# JDA_Compact_Switch_V2.net
KiCad netlist of a schematic drawn in EAGLE
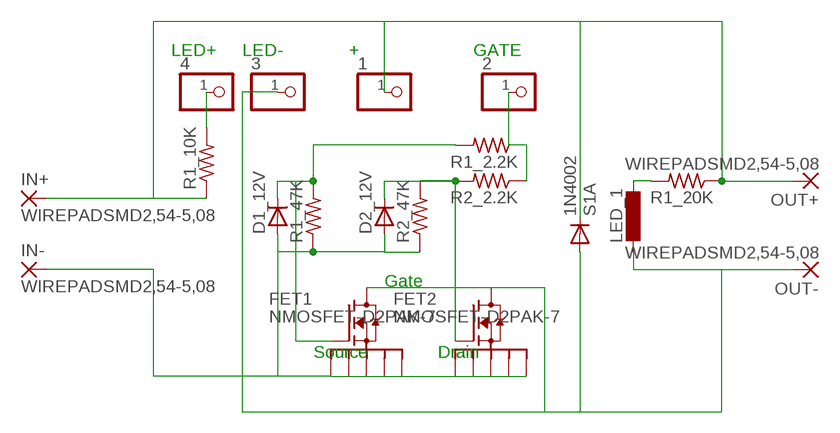
[diagram p0: schematic, sheet 1]

(export (version "E")
  (design (tool "Eeschema 10.0.6"))
  (components
    (comp (ref "1")
      (value "PINHD-1X1")
      (footprint "eagle-import:1X01")
      (libsource (lib "eagle-import") (part "PINHD-1X1"))
    )
    (comp (ref "1N4002")
      (value "S1A")
      (footprint "eagle-import:DO214AC")
      (fields (field (name "MF") "Fairchild"))
      (libsource (lib "eagle-import") (part "S1A"))
    )
    (comp (ref "2")
      (value "PINHD-1X1")
      (footprint "eagle-import:1X01")
      (libsource (lib "eagle-import") (part "PINHD-1X1"))
    )
    (comp (ref "3")
      (value "PINHD-1X1")
      (footprint "eagle-import:1X01")
      (libsource (lib "eagle-import") (part "PINHD-1X1"))
    )
    (comp (ref "4")
      (value "PINHD-1X1")
      (footprint "eagle-import:1X01")
      (libsource (lib "eagle-import") (part "PINHD-1X1"))
    )
    (comp (ref "D1_12V")
      (value "D-SOD-80")
      (footprint "eagle-import:SOD80")
      (libsource (lib "eagle-import") (part "D-SOD-80"))
    )
    (comp (ref "D2_12V")
      (value "D-SOD-80")
      (footprint "eagle-import:SOD80")
      (libsource (lib "eagle-import") (part "D-SOD-80"))
    )
    (comp (ref "FET1")
      (value "NMOSFET-D2PAK-7")
      (footprint "eagle-import:D2PAK-7")
      (libsource (lib "eagle-import") (part "NMOSFET-D2PAK-7"))
    )
    (comp (ref "FET2")
      (value "NMOSFET-D2PAK-7")
      (footprint "eagle-import:D2PAK-7")
      (libsource (lib "eagle-import") (part "NMOSFET-D2PAK-7"))
    )
    (comp (ref "IN+")
      (value "WIREPADSMD2,54-5,08")
      (footprint "eagle-import:SMD2,54-5,08")
      (libsource (lib "eagle-import") (part "WIREPADSMD2,54-5,08"))
    )
    (comp (ref "IN-")
      (value "WIREPADSMD2,54-5,08")
      (footprint "eagle-import:SMD2,54-5,08")
      (libsource (lib "eagle-import") (part "WIREPADSMD2,54-5,08"))
    )
    (comp (ref "LED_1")
      (value "L-EUL0805")
      (footprint "eagle-import:L0805")
      (libsource (lib "eagle-import") (part "L-EUL0805"))
    )
    (comp (ref "OUT+")
      (value "WIREPADSMD2,54-5,08")
      (footprint "eagle-import:SMD2,54-5,08")
      (libsource (lib "eagle-import") (part "WIREPADSMD2,54-5,08"))
    )
    (comp (ref "OUT-")
      (value "WIREPADSMD2,54-5,08")
      (footprint "eagle-import:SMD2,54-5,08")
      (libsource (lib "eagle-import") (part "WIREPADSMD2,54-5,08"))
    )
    (comp (ref "R1_2.2K")
      (value "R-US_M1206")
      (footprint "eagle-import:M1206")
      (libsource (lib "eagle-import") (part "resistor_R-US_M1206"))
    )
    (comp (ref "R1_10K")
      (value "R-US_M1206")
      (footprint "eagle-import:M1206")
      (libsource (lib "eagle-import") (part "resistor_R-US_M1206"))
    )
    (comp (ref "R1_20K")
      (value "R-US_R1206")
      (footprint "eagle-import:R1206")
      (libsource (lib "eagle-import") (part "R-US_R1206"))
    )
    (comp (ref "R1_47K")
      (value "R-US_M1206")
      (footprint "eagle-import:M1206")
      (libsource (lib "eagle-import") (part "resistor_R-US_M1206"))
    )
    (comp (ref "R2_2.2K")
      (value "R-US_M1206")
      (footprint "eagle-import:M1206")
      (libsource (lib "eagle-import") (part "resistor_R-US_M1206"))
    )
    (comp (ref "R2_47K")
      (value "R-US_M1206")
      (footprint "eagle-import:M1206")
      (libsource (lib "eagle-import") (part "resistor_R-US_M1206"))
    )
  )
  (nets
    (net (code "1") (name "Net-(2-Pad1)") (class "Default")
      (node (ref "2") (pin "1") (pinfunction "1_1") (pintype "passive"))
      (node (ref "R1_2.2K") (pin "1") (pinfunction "1_1") (pintype "passive"))
      (node (ref "R2_2.2K") (pin "1") (pinfunction "1_1") (pintype "passive"))
    )
    (net (code "2") (name "Net-(4-Pad1)") (class "Default")
      (node (ref "4") (pin "1") (pinfunction "1_1") (pintype "passive"))
      (node (ref "R1_10K") (pin "2") (pinfunction "2_2") (pintype "passive"))
    )
    (net (code "3") (name "Net-(D1_12V-PadC)") (class "Default")
      (node (ref "D1_12V") (pin "C") (pinfunction "C_C") (pintype "passive"))
      (node (ref "FET1") (pin "G") (pinfunction "G_G") (pintype "passive"))
      (node (ref "R1_2.2K") (pin "2") (pinfunction "2_2") (pintype "passive"))
      (node (ref "R1_47K") (pin "2") (pinfunction "2_2") (pintype "passive"))
    )
    (net (code "4") (name "Net-(D2_12V-PadC)") (class "Default")
      (node (ref "D2_12V") (pin "C") (pinfunction "C_C") (pintype "passive"))
      (node (ref "FET2") (pin "G") (pinfunction "G_G") (pintype "passive"))
      (node (ref "R2_2.2K") (pin "2") (pinfunction "2_2") (pintype "passive"))
      (node (ref "R2_47K") (pin "2") (pinfunction "2_2") (pintype "passive"))
    )
    (net (code "5") (name "Net-(IN+-P)") (class "Default")
      (node (ref "1") (pin "1") (pinfunction "1_1") (pintype "passive"))
      (node (ref "1N4002") (pin "C") (pinfunction "C_C") (pintype "passive"))
      (node (ref "IN+") (pin "1") (pinfunction "P_1") (pintype "passive"))
      (node (ref "OUT+") (pin "1") (pinfunction "P_1") (pintype "passive"))
      (node (ref "R1_10K") (pin "1") (pinfunction "1_1") (pintype "passive"))
      (node (ref "R1_20K") (pin "1") (pinfunction "1_1") (pintype "passive"))
    )
    (net (code "6") (name "Net-(IN--P)") (class "Default")
      (node (ref "D1_12V") (pin "A") (pinfunction "A_A") (pintype "passive"))
      (node (ref "D2_12V") (pin "A") (pinfunction "A_A") (pintype "passive"))
      (node (ref "FET1") (pin "S1") (pinfunction "S1_S1") (pintype "passive"))
      (node (ref "FET1") (pin "S2") (pinfunction "S2_S2") (pintype "passive"))
      (node (ref "FET1") (pin "S3") (pinfunction "S3_S3") (pintype "passive"))
      (node (ref "FET1") (pin "S4") (pinfunction "S4_S4") (pintype "passive"))
      (node (ref "FET1") (pin "S5") (pinfunction "S5_S5") (pintype "passive"))
      (node (ref "FET2") (pin "S1") (pinfunction "S1_S1") (pintype "passive"))
      (node (ref "FET2") (pin "S2") (pinfunction "S2_S2") (pintype "passive"))
      (node (ref "FET2") (pin "S3") (pinfunction "S3_S3") (pintype "passive"))
      (node (ref "FET2") (pin "S4") (pinfunction "S4_S4") (pintype "passive"))
      (node (ref "FET2") (pin "S5") (pinfunction "S5_S5") (pintype "passive"))
      (node (ref "IN-") (pin "1") (pinfunction "P_1") (pintype "passive"))
      (node (ref "R1_47K") (pin "1") (pinfunction "1_1") (pintype "passive"))
      (node (ref "R2_47K") (pin "1") (pinfunction "1_1") (pintype "passive"))
    )
    (net (code "7") (name "Net-(LED_1-Pad1)") (class "Default")
      (node (ref "LED_1") (pin "1") (pinfunction "1_1") (pintype "passive"))
      (node (ref "R1_20K") (pin "2") (pinfunction "2_2") (pintype "passive"))
    )
    (net (code "8") (name "Net-(OUT--P)") (class "Default")
      (node (ref "1N4002") (pin "A") (pinfunction "A_A") (pintype "passive"))
      (node (ref "3") (pin "1") (pinfunction "1_1") (pintype "passive"))
      (node (ref "FET1") (pin "D") (pinfunction "D_D") (pintype "passive"))
      (node (ref "FET2") (pin "D") (pinfunction "D_D") (pintype "passive"))
      (node (ref "LED_1") (pin "2") (pinfunction "2_2") (pintype "passive"))
      (node (ref "OUT-") (pin "1") (pinfunction "P_1") (pintype "passive"))
    )
  )
)
